# Hex-pendant-apa102-v1a.net
KiCad netlist of a schematic drawn in EAGLE
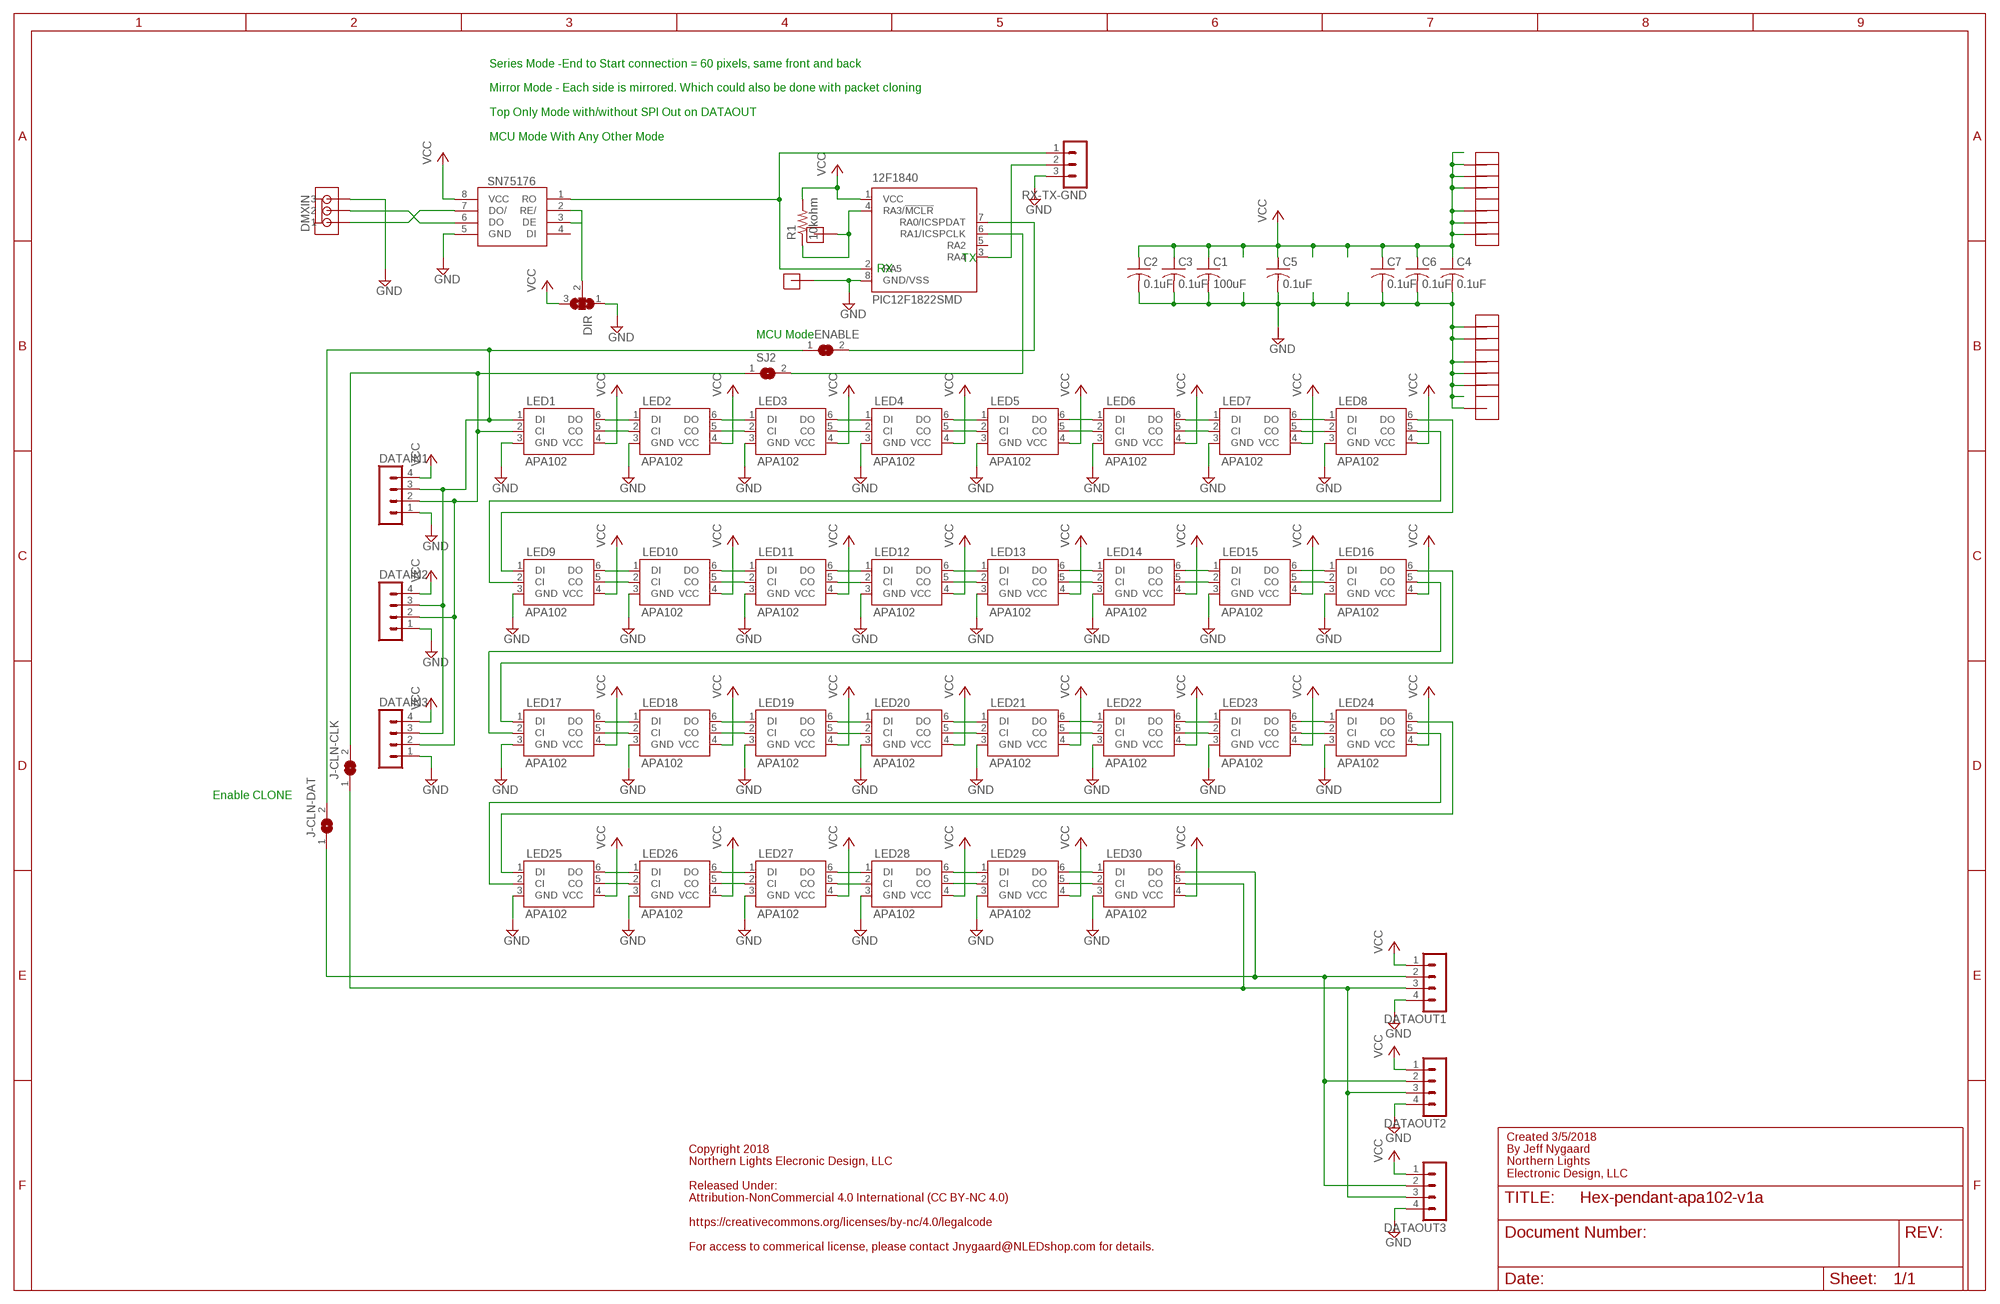
[diagram p0: schematic, sheet 1]

(export (version "E")
  (design (tool "Eeschema 10.0.6"))
  (components
    (comp (ref "12F1840")
      (value "PIC12F1822SMD")
      (footprint "eagle-import:SO-08")
      (fields (field (name "MF") "MICROCHIP") (field (name "MPN") "PIC12F675-E/SN"))
      (libsource (lib "eagle-import") (part "PIC12F1822SMD"))
    )
    (comp (ref "BUTTGND")
      (value "JUMPER")
      (footprint "eagle-import:JUMPER")
      (libsource (lib "eagle-import") (part "JUMPER"))
    )
    (comp (ref "BUTTON")
      (value "JUMPER")
      (footprint "eagle-import:JUMPER")
      (libsource (lib "eagle-import") (part "JUMPER"))
    )
    (comp (ref "C1")
      (value "100uF")
      (footprint "eagle-import:C1206")
      (libsource (lib "eagle-import") (part "C-USC1206"))
    )
    (comp (ref "C2")
      (value "0.1uF")
      (footprint "eagle-import:C1206")
      (libsource (lib "eagle-import") (part "C-USC1206"))
    )
    (comp (ref "C3")
      (value "0.1uF")
      (footprint "eagle-import:C1206")
      (libsource (lib "eagle-import") (part "C-USC1206"))
    )
    (comp (ref "C4")
      (value "0.1uF")
      (footprint "eagle-import:C1206")
      (libsource (lib "eagle-import") (part "C-USC1206"))
    )
    (comp (ref "C5")
      (value "0.1uF")
      (footprint "eagle-import:C1206")
      (libsource (lib "eagle-import") (part "C-USC1206"))
    )
    (comp (ref "C6")
      (value "0.1uF")
      (footprint "eagle-import:C1206")
      (libsource (lib "eagle-import") (part "C-USC1206"))
    )
    (comp (ref "C7")
      (value "0.1uF")
      (footprint "eagle-import:C1206")
      (libsource (lib "eagle-import") (part "C-USC1206"))
    )
    (comp (ref "DATAIN1")
      (value "MA04-1")
      (footprint "eagle-import:MA04-1")
      (libsource (lib "eagle-import") (part "MA04-1"))
    )
    (comp (ref "DATAIN2")
      (value "MA04-1")
      (footprint "eagle-import:MA04-1")
      (libsource (lib "eagle-import") (part "MA04-1"))
    )
    (comp (ref "DATAIN3")
      (value "MA04-1")
      (footprint "eagle-import:MA04-1")
      (libsource (lib "eagle-import") (part "MA04-1"))
    )
    (comp (ref "DATAOUT1")
      (value "MA04-1")
      (footprint "eagle-import:MA04-1")
      (libsource (lib "eagle-import") (part "MA04-1"))
    )
    (comp (ref "DATAOUT2")
      (value "MA04-1")
      (footprint "eagle-import:MA04-1")
      (libsource (lib "eagle-import") (part "MA04-1"))
    )
    (comp (ref "DATAOUT3")
      (value "MA04-1")
      (footprint "eagle-import:MA04-1")
      (libsource (lib "eagle-import") (part "MA04-1"))
    )
    (comp (ref "DIR")
      (value "SJ2W")
      (footprint "eagle-import:SJ_2")
      (libsource (lib "eagle-import") (part "SJ2W"))
    )
    (comp (ref "DMXIN")
      (value "MOLEXKK3")
      (footprint "eagle-import:MOLEXKK3")
      (libsource (lib "eagle-import") (part "MOLEXKK3"))
    )
    (comp (ref "ENABLE")
      (value "SJ")
      (footprint "eagle-import:SJ")
      (libsource (lib "eagle-import") (part "SJ"))
    )
    (comp (ref "J-CLN-CLK")
      (value "SJ")
      (footprint "eagle-import:SJ")
      (libsource (lib "eagle-import") (part "SJ"))
    )
    (comp (ref "J-CLN-DAT")
      (value "SJ")
      (footprint "eagle-import:SJ")
      (libsource (lib "eagle-import") (part "SJ"))
    )
    (comp (ref "JGND1")
      (value "1HEADER")
      (footprint "eagle-import:J1")
      (libsource (lib "eagle-import") (part "1HEADER"))
    )
    (comp (ref "JGND3")
      (value "1HEADER")
      (footprint "eagle-import:J1")
      (libsource (lib "eagle-import") (part "1HEADER"))
    )
    (comp (ref "JGND4")
      (value "1HEADER")
      (footprint "eagle-import:J1")
      (libsource (lib "eagle-import") (part "1HEADER"))
    )
    (comp (ref "JGND5")
      (value "1HEADER")
      (footprint "eagle-import:J1")
      (libsource (lib "eagle-import") (part "1HEADER"))
    )
    (comp (ref "JGND6")
      (value "1HEADER")
      (footprint "eagle-import:J1")
      (libsource (lib "eagle-import") (part "1HEADER"))
    )
    (comp (ref "JGND7")
      (value "1HEADER")
      (footprint "eagle-import:J1")
      (libsource (lib "eagle-import") (part "1HEADER"))
    )
    (comp (ref "JVCC1")
      (value "1HEADER")
      (footprint "eagle-import:J1")
      (libsource (lib "eagle-import") (part "1HEADER"))
    )
    (comp (ref "JVCC2")
      (value "1HEADER")
      (footprint "eagle-import:J1")
      (libsource (lib "eagle-import") (part "1HEADER"))
    )
    (comp (ref "JVCC3")
      (value "1HEADER")
      (footprint "eagle-import:J1")
      (libsource (lib "eagle-import") (part "1HEADER"))
    )
    (comp (ref "JVCC4")
      (value "1HEADER")
      (footprint "eagle-import:J1")
      (libsource (lib "eagle-import") (part "1HEADER"))
    )
    (comp (ref "JVCC5")
      (value "1HEADER")
      (footprint "eagle-import:J1")
      (libsource (lib "eagle-import") (part "1HEADER"))
    )
    (comp (ref "JVCC6")
      (value "1HEADER")
      (footprint "eagle-import:J1")
      (libsource (lib "eagle-import") (part "1HEADER"))
    )
    (comp (ref "LED1")
      (value "APA102")
      (footprint "eagle-import:APA102")
      (libsource (lib "eagle-import") (part "APA102"))
    )
    (comp (ref "LED2")
      (value "APA102")
      (footprint "eagle-import:APA102")
      (libsource (lib "eagle-import") (part "APA102"))
    )
    (comp (ref "LED3")
      (value "APA102")
      (footprint "eagle-import:APA102")
      (libsource (lib "eagle-import") (part "APA102"))
    )
    (comp (ref "LED4")
      (value "APA102")
      (footprint "eagle-import:APA102")
      (libsource (lib "eagle-import") (part "APA102"))
    )
    (comp (ref "LED5")
      (value "APA102")
      (footprint "eagle-import:APA102")
      (libsource (lib "eagle-import") (part "APA102"))
    )
    (comp (ref "LED6")
      (value "APA102")
      (footprint "eagle-import:APA102")
      (libsource (lib "eagle-import") (part "APA102"))
    )
    (comp (ref "LED7")
      (value "APA102")
      (footprint "eagle-import:APA102")
      (libsource (lib "eagle-import") (part "APA102"))
    )
    (comp (ref "LED8")
      (value "APA102")
      (footprint "eagle-import:APA102")
      (libsource (lib "eagle-import") (part "APA102"))
    )
    (comp (ref "LED9")
      (value "APA102")
      (footprint "eagle-import:APA102")
      (libsource (lib "eagle-import") (part "APA102"))
    )
    (comp (ref "LED10")
      (value "APA102")
      (footprint "eagle-import:APA102")
      (libsource (lib "eagle-import") (part "APA102"))
    )
    (comp (ref "LED11")
      (value "APA102")
      (footprint "eagle-import:APA102")
      (libsource (lib "eagle-import") (part "APA102"))
    )
    (comp (ref "LED12")
      (value "APA102")
      (footprint "eagle-import:APA102")
      (libsource (lib "eagle-import") (part "APA102"))
    )
    (comp (ref "LED13")
      (value "APA102")
      (footprint "eagle-import:APA102")
      (libsource (lib "eagle-import") (part "APA102"))
    )
    (comp (ref "LED14")
      (value "APA102")
      (footprint "eagle-import:APA102")
      (libsource (lib "eagle-import") (part "APA102"))
    )
    (comp (ref "LED15")
      (value "APA102")
      (footprint "eagle-import:APA102")
      (libsource (lib "eagle-import") (part "APA102"))
    )
    (comp (ref "LED16")
      (value "APA102")
      (footprint "eagle-import:APA102")
      (libsource (lib "eagle-import") (part "APA102"))
    )
    (comp (ref "LED17")
      (value "APA102")
      (footprint "eagle-import:APA102")
      (libsource (lib "eagle-import") (part "APA102"))
    )
    (comp (ref "LED18")
      (value "APA102")
      (footprint "eagle-import:APA102")
      (libsource (lib "eagle-import") (part "APA102"))
    )
    (comp (ref "LED19")
      (value "APA102")
      (footprint "eagle-import:APA102")
      (libsource (lib "eagle-import") (part "APA102"))
    )
    (comp (ref "LED20")
      (value "APA102")
      (footprint "eagle-import:APA102")
      (libsource (lib "eagle-import") (part "APA102"))
    )
    (comp (ref "LED21")
      (value "APA102")
      (footprint "eagle-import:APA102")
      (libsource (lib "eagle-import") (part "APA102"))
    )
    (comp (ref "LED22")
      (value "APA102")
      (footprint "eagle-import:APA102")
      (libsource (lib "eagle-import") (part "APA102"))
    )
    (comp (ref "LED23")
      (value "APA102")
      (footprint "eagle-import:APA102")
      (libsource (lib "eagle-import") (part "APA102"))
    )
    (comp (ref "LED24")
      (value "APA102")
      (footprint "eagle-import:APA102")
      (libsource (lib "eagle-import") (part "APA102"))
    )
    (comp (ref "LED25")
      (value "APA102")
      (footprint "eagle-import:APA102")
      (libsource (lib "eagle-import") (part "APA102"))
    )
    (comp (ref "LED26")
      (value "APA102")
      (footprint "eagle-import:APA102")
      (libsource (lib "eagle-import") (part "APA102"))
    )
    (comp (ref "LED27")
      (value "APA102")
      (footprint "eagle-import:APA102")
      (libsource (lib "eagle-import") (part "APA102"))
    )
    (comp (ref "LED28")
      (value "APA102")
      (footprint "eagle-import:APA102")
      (libsource (lib "eagle-import") (part "APA102"))
    )
    (comp (ref "LED29")
      (value "APA102")
      (footprint "eagle-import:APA102")
      (libsource (lib "eagle-import") (part "APA102"))
    )
    (comp (ref "LED30")
      (value "APA102")
      (footprint "eagle-import:APA102")
      (libsource (lib "eagle-import") (part "APA102"))
    )
    (comp (ref "R1")
      (value "10kohm")
      (footprint "eagle-import:R1206")
      (libsource (lib "eagle-import") (part "R-US_R1206"))
    )
    (comp (ref "RX-TX-GND")
      (value "MA03-12")
      (footprint "eagle-import:MA03-1-V2")
      (libsource (lib "eagle-import") (part "MA03-12"))
    )
    (comp (ref "SJ2") (value "SJ") (footprint "eagle-import:SJ") (libsource (lib "eagle-import") (part "SJ")))
    (comp (ref "TRANSCEIVER")
      (value "SN75176SMD")
      (footprint "eagle-import:SOIC-8")
      (libsource (lib "eagle-import") (part "SN75176SMD"))
    )
  )
  (nets
    (net (code "1") (name "GND") (class "Default")
      (node (ref "12F1840") (pin "8") (pinfunction "GND/VSS_8") (pintype "power_in"))
      (node (ref "BUTTGND") (pin "2") (pinfunction "J1_2") (pintype "bidirectional"))
      (node (ref "C1") (pin "2") (pinfunction "2_2") (pintype "passive"))
      (node (ref "C2") (pin "2") (pinfunction "2_2") (pintype "passive"))
      (node (ref "C3") (pin "2") (pinfunction "2_2") (pintype "passive"))
      (node (ref "C4") (pin "2") (pinfunction "2_2") (pintype "passive"))
      (node (ref "C5") (pin "2") (pinfunction "2_2") (pintype "passive"))
      (node (ref "C6") (pin "2") (pinfunction "2_2") (pintype "passive"))
      (node (ref "C7") (pin "2") (pinfunction "2_2") (pintype "passive"))
      (node (ref "DATAIN1") (pin "1") (pinfunction "1_1") (pintype "passive"))
      (node (ref "DATAIN2") (pin "1") (pinfunction "1_1") (pintype "passive"))
      (node (ref "DATAIN3") (pin "1") (pinfunction "1_1") (pintype "passive"))
      (node (ref "DATAOUT1") (pin "4") (pinfunction "4_4") (pintype "passive"))
      (node (ref "DATAOUT2") (pin "4") (pinfunction "4_4") (pintype "passive"))
      (node (ref "DATAOUT3") (pin "4") (pinfunction "4_4") (pintype "passive"))
      (node (ref "DIR") (pin "1") (pinfunction "1_1") (pintype "passive"))
      (node (ref "DMXIN") (pin "3") (pinfunction "3_3") (pintype "bidirectional"))
      (node (ref "JGND1") (pin "2") (pinfunction "J1_2") (pintype "bidirectional"))
      (node (ref "JGND3") (pin "2") (pinfunction "J1_2") (pintype "bidirectional"))
      (node (ref "JGND4") (pin "2") (pinfunction "J1_2") (pintype "bidirectional"))
      (node (ref "JGND6") (pin "2") (pinfunction "J1_2") (pintype "bidirectional"))
      (node (ref "JGND7") (pin "2") (pinfunction "J1_2") (pintype "bidirectional"))
      (node (ref "JVCC4") (pin "2") (pinfunction "J1_2") (pintype "bidirectional"))
      (node (ref "LED1") (pin "3") (pinfunction "GND_3") (pintype "bidirectional"))
      (node (ref "LED10") (pin "3") (pinfunction "GND_3") (pintype "bidirectional"))
      (node (ref "LED11") (pin "3") (pinfunction "GND_3") (pintype "bidirectional"))
      (node (ref "LED12") (pin "3") (pinfunction "GND_3") (pintype "bidirectional"))
      (node (ref "LED13") (pin "3") (pinfunction "GND_3") (pintype "bidirectional"))
      (node (ref "LED14") (pin "3") (pinfunction "GND_3") (pintype "bidirectional"))
      (node (ref "LED15") (pin "3") (pinfunction "GND_3") (pintype "bidirectional"))
      (node (ref "LED16") (pin "3") (pinfunction "GND_3") (pintype "bidirectional"))
      (node (ref "LED17") (pin "3") (pinfunction "GND_3") (pintype "bidirectional"))
      (node (ref "LED18") (pin "3") (pinfunction "GND_3") (pintype "bidirectional"))
      (node (ref "LED19") (pin "3") (pinfunction "GND_3") (pintype "bidirectional"))
      (node (ref "LED2") (pin "3") (pinfunction "GND_3") (pintype "bidirectional"))
      (node (ref "LED20") (pin "3") (pinfunction "GND_3") (pintype "bidirectional"))
      (node (ref "LED21") (pin "3") (pinfunction "GND_3") (pintype "bidirectional"))
      (node (ref "LED22") (pin "3") (pinfunction "GND_3") (pintype "bidirectional"))
      (node (ref "LED23") (pin "3") (pinfunction "GND_3") (pintype "bidirectional"))
      (node (ref "LED24") (pin "3") (pinfunction "GND_3") (pintype "bidirectional"))
      (node (ref "LED25") (pin "3") (pinfunction "GND_3") (pintype "bidirectional"))
      (node (ref "LED26") (pin "3") (pinfunction "GND_3") (pintype "bidirectional"))
      (node (ref "LED27") (pin "3") (pinfunction "GND_3") (pintype "bidirectional"))
      (node (ref "LED28") (pin "3") (pinfunction "GND_3") (pintype "bidirectional"))
      (node (ref "LED29") (pin "3") (pinfunction "GND_3") (pintype "bidirectional"))
      (node (ref "LED3") (pin "3") (pinfunction "GND_3") (pintype "bidirectional"))
      (node (ref "LED30") (pin "3") (pinfunction "GND_3") (pintype "bidirectional"))
      (node (ref "LED4") (pin "3") (pinfunction "GND_3") (pintype "bidirectional"))
      (node (ref "LED5") (pin "3") (pinfunction "GND_3") (pintype "bidirectional"))
      (node (ref "LED6") (pin "3") (pinfunction "GND_3") (pintype "bidirectional"))
      (node (ref "LED7") (pin "3") (pinfunction "GND_3") (pintype "bidirectional"))
      (node (ref "LED8") (pin "3") (pinfunction "GND_3") (pintype "bidirectional"))
      (node (ref "LED9") (pin "3") (pinfunction "GND_3") (pintype "bidirectional"))
      (node (ref "RX-TX-GND") (pin "3") (pinfunction "3_3") (pintype "passive"))
      (node (ref "TRANSCEIVER") (pin "5") (pinfunction "GND_5") (pintype "bidirectional"))
    )
    (net (code "2") (name "Net-(12F1840-RA0{slash}ICSPDAT)") (class "Default")
      (node (ref "12F1840") (pin "7") (pinfunction "RA0/ICSPDAT_7") (pintype "bidirectional"))
      (node (ref "ENABLE") (pin "2") (pinfunction "2_2") (pintype "passive"))
    )
    (net (code "3") (name "Net-(12F1840-RA1{slash}ICSPCLK)") (class "Default")
      (node (ref "12F1840") (pin "6") (pinfunction "RA1/ICSPCLK_6") (pintype "bidirectional"))
      (node (ref "SJ2") (pin "2") (pinfunction "2_2") (pintype "passive"))
    )
    (net (code "4") (name "Net-(12F1840-RA3{slash}~{MCLR})") (class "Default")
      (node (ref "12F1840") (pin "4") (pinfunction "RA3/~{MCLR}_4") (pintype "input"))
      (node (ref "BUTTON") (pin "2") (pinfunction "J1_2") (pintype "bidirectional"))
      (node (ref "R1") (pin "1") (pinfunction "1_1") (pintype "passive"))
    )
    (net (code "5") (name "Net-(12F1840-RA4)") (class "Default")
      (node (ref "12F1840") (pin "3") (pinfunction "RA4_3") (pintype "bidirectional"))
      (node (ref "RX-TX-GND") (pin "2") (pinfunction "2_2") (pintype "passive"))
    )
    (net (code "6") (name "Net-(12F1840-RA5)") (class "Default")
      (node (ref "12F1840") (pin "2") (pinfunction "RA5_2") (pintype "bidirectional"))
      (node (ref "RX-TX-GND") (pin "1") (pinfunction "1_1") (pintype "passive"))
      (node (ref "TRANSCEIVER") (pin "1") (pinfunction "RO_1") (pintype "bidirectional"))
    )
    (net (code "7") (name "Net-(LED1-CI)") (class "Default")
      (node (ref "DATAIN1") (pin "2") (pinfunction "2_2") (pintype "passive"))
      (node (ref "DATAIN2") (pin "2") (pinfunction "2_2") (pintype "passive"))
      (node (ref "DATAIN3") (pin "2") (pinfunction "2_2") (pintype "passive"))
      (node (ref "J-CLN-CLK") (pin "2") (pinfunction "2_2") (pintype "passive"))
      (node (ref "LED1") (pin "2") (pinfunction "CI_2") (pintype "bidirectional"))
      (node (ref "SJ2") (pin "1") (pinfunction "1_1") (pintype "passive"))
    )
    (net (code "8") (name "Net-(LED1-CO)") (class "Default")
      (node (ref "LED1") (pin "5") (pinfunction "CO_5") (pintype "bidirectional"))
      (node (ref "LED2") (pin "2") (pinfunction "CI_2") (pintype "bidirectional"))
    )
    (net (code "9") (name "Net-(LED1-DI)") (class "Default")
      (node (ref "DATAIN1") (pin "3") (pinfunction "3_3") (pintype "passive"))
      (node (ref "DATAIN2") (pin "3") (pinfunction "3_3") (pintype "passive"))
      (node (ref "DATAIN3") (pin "3") (pinfunction "3_3") (pintype "passive"))
      (node (ref "ENABLE") (pin "1") (pinfunction "1_1") (pintype "passive"))
      (node (ref "J-CLN-DAT") (pin "2") (pinfunction "2_2") (pintype "passive"))
      (node (ref "LED1") (pin "1") (pinfunction "DI_1") (pintype "bidirectional"))
    )
    (net (code "10") (name "Net-(LED1-DO)") (class "Default")
      (node (ref "LED1") (pin "6") (pinfunction "DO_6") (pintype "bidirectional"))
      (node (ref "LED2") (pin "1") (pinfunction "DI_1") (pintype "bidirectional"))
    )
    (net (code "11") (name "Net-(LED2-CO)") (class "Default")
      (node (ref "LED2") (pin "5") (pinfunction "CO_5") (pintype "bidirectional"))
      (node (ref "LED3") (pin "2") (pinfunction "CI_2") (pintype "bidirectional"))
    )
    (net (code "12") (name "Net-(LED2-DO)") (class "Default")
      (node (ref "LED2") (pin "6") (pinfunction "DO_6") (pintype "bidirectional"))
      (node (ref "LED3") (pin "1") (pinfunction "DI_1") (pintype "bidirectional"))
    )
    (net (code "13") (name "Net-(LED3-CO)") (class "Default")
      (node (ref "LED3") (pin "5") (pinfunction "CO_5") (pintype "bidirectional"))
      (node (ref "LED4") (pin "2") (pinfunction "CI_2") (pintype "bidirectional"))
    )
    (net (code "14") (name "Net-(LED3-DO)") (class "Default")
      (node (ref "LED3") (pin "6") (pinfunction "DO_6") (pintype "bidirectional"))
      (node (ref "LED4") (pin "1") (pinfunction "DI_1") (pintype "bidirectional"))
    )
    (net (code "15") (name "Net-(LED4-CO)") (class "Default")
      (node (ref "LED4") (pin "5") (pinfunction "CO_5") (pintype "bidirectional"))
      (node (ref "LED5") (pin "2") (pinfunction "CI_2") (pintype "bidirectional"))
    )
    (net (code "16") (name "Net-(LED4-DO)") (class "Default")
      (node (ref "LED4") (pin "6") (pinfunction "DO_6") (pintype "bidirectional"))
      (node (ref "LED5") (pin "1") (pinfunction "DI_1") (pintype "bidirectional"))
    )
    (net (code "17") (name "Net-(LED5-CO)") (class "Default")
      (node (ref "LED5") (pin "5") (pinfunction "CO_5") (pintype "bidirectional"))
      (node (ref "LED6") (pin "2") (pinfunction "CI_2") (pintype "bidirectional"))
    )
    (net (code "18") (name "Net-(LED5-DO)") (class "Default")
      (node (ref "LED5") (pin "6") (pinfunction "DO_6") (pintype "bidirectional"))
      (node (ref "LED6") (pin "1") (pinfunction "DI_1") (pintype "bidirectional"))
    )
    (net (code "19") (name "Net-(LED6-CO)") (class "Default")
      (node (ref "LED6") (pin "5") (pinfunction "CO_5") (pintype "bidirectional"))
      (node (ref "LED7") (pin "2") (pinfunction "CI_2") (pintype "bidirectional"))
    )
    (net (code "20") (name "Net-(LED6-DO)") (class "Default")
      (node (ref "LED6") (pin "6") (pinfunction "DO_6") (pintype "bidirectional"))
      (node (ref "LED7") (pin "1") (pinfunction "DI_1") (pintype "bidirectional"))
    )
    (net (code "21") (name "Net-(LED7-CO)") (class "Default")
      (node (ref "LED7") (pin "5") (pinfunction "CO_5") (pintype "bidirectional"))
      (node (ref "LED8") (pin "2") (pinfunction "CI_2") (pintype "bidirectional"))
    )
    (net (code "22") (name "Net-(LED7-DO)") (class "Default")
      (node (ref "LED7") (pin "6") (pinfunction "DO_6") (pintype "bidirectional"))
      (node (ref "LED8") (pin "1") (pinfunction "DI_1") (pintype "bidirectional"))
    )
    (net (code "23") (name "Net-(LED8-CO)") (class "Default")
      (node (ref "LED8") (pin "5") (pinfunction "CO_5") (pintype "bidirectional"))
      (node (ref "LED9") (pin "2") (pinfunction "CI_2") (pintype "bidirectional"))
    )
    (net (code "24") (name "Net-(LED8-DO)") (class "Default")
      (node (ref "LED8") (pin "6") (pinfunction "DO_6") (pintype "bidirectional"))
      (node (ref "LED9") (pin "1") (pinfunction "DI_1") (pintype "bidirectional"))
    )
    (net (code "25") (name "Net-(LED10-CI)") (class "Default")
      (node (ref "LED10") (pin "2") (pinfunction "CI_2") (pintype "bidirectional"))
      (node (ref "LED9") (pin "5") (pinfunction "CO_5") (pintype "bidirectional"))
    )
    (net (code "26") (name "Net-(LED10-CO)") (class "Default")
      (node (ref "LED10") (pin "5") (pinfunction "CO_5") (pintype "bidirectional"))
      (node (ref "LED11") (pin "2") (pinfunction "CI_2") (pintype "bidirectional"))
    )
    (net (code "27") (name "Net-(LED10-DI)") (class "Default")
      (node (ref "LED10") (pin "1") (pinfunction "DI_1") (pintype "bidirectional"))
      (node (ref "LED9") (pin "6") (pinfunction "DO_6") (pintype "bidirectional"))
    )
    (net (code "28") (name "Net-(LED10-DO)") (class "Default")
      (node (ref "LED10") (pin "6") (pinfunction "DO_6") (pintype "bidirectional"))
      (node (ref "LED11") (pin "1") (pinfunction "DI_1") (pintype "bidirectional"))
    )
    (net (code "29") (name "Net-(LED11-CO)") (class "Default")
      (node (ref "LED11") (pin "5") (pinfunction "CO_5") (pintype "bidirectional"))
      (node (ref "LED12") (pin "2") (pinfunction "CI_2") (pintype "bidirectional"))
    )
    (net (code "30") (name "Net-(LED11-DO)") (class "Default")
      (node (ref "LED11") (pin "6") (pinfunction "DO_6") (pintype "bidirectional"))
      (node (ref "LED12") (pin "1") (pinfunction "DI_1") (pintype "bidirectional"))
    )
    (net (code "31") (name "Net-(LED12-CO)") (class "Default")
      (node (ref "LED12") (pin "5") (pinfunction "CO_5") (pintype "bidirectional"))
      (node (ref "LED13") (pin "2") (pinfunction "CI_2") (pintype "bidirectional"))
    )
    (net (code "32") (name "Net-(LED12-DO)") (class "Default")
      (node (ref "LED12") (pin "6") (pinfunction "DO_6") (pintype "bidirectional"))
      (node (ref "LED13") (pin "1") (pinfunction "DI_1") (pintype "bidirectional"))
    )
    (net (code "33") (name "Net-(LED13-CO)") (class "Default")
      (node (ref "LED13") (pin "5") (pinfunction "CO_5") (pintype "bidirectional"))
      (node (ref "LED14") (pin "2") (pinfunction "CI_2") (pintype "bidirectional"))
    )
    (net (code "34") (name "Net-(LED13-DO)") (class "Default")
      (node (ref "LED13") (pin "6") (pinfunction "DO_6") (pintype "bidirectional"))
      (node (ref "LED14") (pin "1") (pinfunction "DI_1") (pintype "bidirectional"))
    )
    (net (code "35") (name "Net-(LED14-CO)") (class "Default")
      (node (ref "LED14") (pin "5") (pinfunction "CO_5") (pintype "bidirectional"))
      (node (ref "LED15") (pin "2") (pinfunction "CI_2") (pintype "bidirectional"))
    )
    (net (code "36") (name "Net-(LED14-DO)") (class "Default")
      (node (ref "LED14") (pin "6") (pinfunction "DO_6") (pintype "bidirectional"))
      (node (ref "LED15") (pin "1") (pinfunction "DI_1") (pintype "bidirectional"))
    )
    (net (code "37") (name "Net-(LED15-CO)") (class "Default")
      (node (ref "LED15") (pin "5") (pinfunction "CO_5") (pintype "bidirectional"))
      (node (ref "LED16") (pin "2") (pinfunction "CI_2") (pintype "bidirectional"))
    )
    (net (code "38") (name "Net-(LED15-DO)") (class "Default")
      (node (ref "LED15") (pin "6") (pinfunction "DO_6") (pintype "bidirectional"))
      (node (ref "LED16") (pin "1") (pinfunction "DI_1") (pintype "bidirectional"))
    )
    (net (code "39") (name "Net-(LED16-CO)") (class "Default")
      (node (ref "LED16") (pin "5") (pinfunction "CO_5") (pintype "bidirectional"))
      (node (ref "LED17") (pin "2") (pinfunction "CI_2") (pintype "bidirectional"))
    )
    (net (code "40") (name "Net-(LED16-DO)") (class "Default")
      (node (ref "LED16") (pin "6") (pinfunction "DO_6") (pintype "bidirectional"))
      (node (ref "LED17") (pin "1") (pinfunction "DI_1") (pintype "bidirectional"))
    )
    (net (code "41") (name "Net-(LED17-CO)") (class "Default")
      (node (ref "LED17") (pin "5") (pinfunction "CO_5") (pintype "bidirectional"))
      (node (ref "LED18") (pin "2") (pinfunction "CI_2") (pintype "bidirectional"))
    )
    (net (code "42") (name "Net-(LED17-DO)") (class "Default")
      (node (ref "LED17") (pin "6") (pinfunction "DO_6") (pintype "bidirectional"))
      (node (ref "LED18") (pin "1") (pinfunction "DI_1") (pintype "bidirectional"))
    )
    (net (code "43") (name "Net-(LED18-CO)") (class "Default")
      (node (ref "LED18") (pin "5") (pinfunction "CO_5") (pintype "bidirectional"))
      (node (ref "LED19") (pin "2") (pinfunction "CI_2") (pintype "bidirectional"))
    )
    (net (code "44") (name "Net-(LED18-DO)") (class "Default")
      (node (ref "LED18") (pin "6") (pinfunction "DO_6") (pintype "bidirectional"))
      (node (ref "LED19") (pin "1") (pinfunction "DI_1") (pintype "bidirectional"))
    )
    (net (code "45") (name "Net-(LED19-CO)") (class "Default")
      (node (ref "LED19") (pin "5") (pinfunction "CO_5") (pintype "bidirectional"))
      (node (ref "LED20") (pin "2") (pinfunction "CI_2") (pintype "bidirectional"))
    )
    (net (code "46") (name "Net-(LED19-DO)") (class "Default")
      (node (ref "LED19") (pin "6") (pinfunction "DO_6") (pintype "bidirectional"))
      (node (ref "LED20") (pin "1") (pinfunction "DI_1") (pintype "bidirectional"))
    )
    (net (code "47") (name "Net-(LED20-CO)") (class "Default")
      (node (ref "LED20") (pin "5") (pinfunction "CO_5") (pintype "bidirectional"))
      (node (ref "LED21") (pin "2") (pinfunction "CI_2") (pintype "bidirectional"))
    )
    (net (code "48") (name "Net-(LED20-DO)") (class "Default")
      (node (ref "LED20") (pin "6") (pinfunction "DO_6") (pintype "bidirectional"))
      (node (ref "LED21") (pin "1") (pinfunction "DI_1") (pintype "bidirectional"))
    )
    (net (code "49") (name "Net-(LED21-CO)") (class "Default")
      (node (ref "LED21") (pin "5") (pinfunction "CO_5") (pintype "bidirectional"))
      (node (ref "LED22") (pin "2") (pinfunction "CI_2") (pintype "bidirectional"))
    )
    (net (code "50") (name "Net-(LED21-DO)") (class "Default")
      (node (ref "LED21") (pin "6") (pinfunction "DO_6") (pintype "bidirectional"))
      (node (ref "LED22") (pin "1") (pinfunction "DI_1") (pintype "bidirectional"))
    )
    (net (code "51") (name "Net-(LED22-CO)") (class "Default")
      (node (ref "LED22") (pin "5") (pinfunction "CO_5") (pintype "bidirectional"))
      (node (ref "LED23") (pin "2") (pinfunction "CI_2") (pintype "bidirectional"))
    )
    (net (code "52") (name "Net-(LED22-DO)") (class "Default")
      (node (ref "LED22") (pin "6") (pinfunction "DO_6") (pintype "bidirectional"))
      (node (ref "LED23") (pin "1") (pinfunction "DI_1") (pintype "bidirectional"))
    )
    (net (code "53") (name "Net-(LED23-CO)") (class "Default")
      (node (ref "LED23") (pin "5") (pinfunction "CO_5") (pintype "bidirectional"))
      (node (ref "LED24") (pin "2") (pinfunction "CI_2") (pintype "bidirectional"))
    )
    (net (code "54") (name "Net-(LED23-DO)") (class "Default")
      (node (ref "LED23") (pin "6") (pinfunction "DO_6") (pintype "bidirectional"))
      (node (ref "LED24") (pin "1") (pinfunction "DI_1") (pintype "bidirectional"))
    )
    (net (code "55") (name "Net-(LED24-CO)") (class "Default")
      (node (ref "LED24") (pin "5") (pinfunction "CO_5") (pintype "bidirectional"))
      (node (ref "LED25") (pin "2") (pinfunction "CI_2") (pintype "bidirectional"))
    )
    (net (code "56") (name "Net-(LED24-DO)") (class "Default")
      (node (ref "LED24") (pin "6") (pinfunction "DO_6") (pintype "bidirectional"))
      (node (ref "LED25") (pin "1") (pinfunction "DI_1") (pintype "bidirectional"))
    )
    (net (code "57") (name "Net-(LED25-CO)") (class "Default")
      (node (ref "LED25") (pin "5") (pinfunction "CO_5") (pintype "bidirectional"))
      (node (ref "LED26") (pin "2") (pinfunction "CI_2") (pintype "bidirectional"))
    )
    (net (code "58") (name "Net-(LED25-DO)") (class "Default")
      (node (ref "LED25") (pin "6") (pinfunction "DO_6") (pintype "bidirectional"))
      (node (ref "LED26") (pin "1") (pinfunction "DI_1") (pintype "bidirectional"))
    )
    (net (code "59") (name "Net-(LED26-CO)") (class "Default")
      (node (ref "LED26") (pin "5") (pinfunction "CO_5") (pintype "bidirectional"))
      (node (ref "LED27") (pin "2") (pinfunction "CI_2") (pintype "bidirectional"))
    )
    (net (code "60") (name "Net-(LED26-DO)") (class "Default")
      (node (ref "LED26") (pin "6") (pinfunction "DO_6") (pintype "bidirectional"))
      (node (ref "LED27") (pin "1") (pinfunction "DI_1") (pintype "bidirectional"))
    )
    (net (code "61") (name "Net-(LED27-CO)") (class "Default")
      (node (ref "LED27") (pin "5") (pinfunction "CO_5") (pintype "bidirectional"))
      (node (ref "LED28") (pin "2") (pinfunction "CI_2") (pintype "bidirectional"))
    )
    (net (code "62") (name "Net-(LED27-DO)") (class "Default")
      (node (ref "LED27") (pin "6") (pinfunction "DO_6") (pintype "bidirectional"))
      (node (ref "LED28") (pin "1") (pinfunction "DI_1") (pintype "bidirectional"))
    )
    (net (code "63") (name "Net-(LED28-CO)") (class "Default")
      (node (ref "LED28") (pin "5") (pinfunction "CO_5") (pintype "bidirectional"))
      (node (ref "LED29") (pin "2") (pinfunction "CI_2") (pintype "bidirectional"))
    )
    (net (code "64") (name "Net-(LED28-DO)") (class "Default")
      (node (ref "LED28") (pin "6") (pinfunction "DO_6") (pintype "bidirectional"))
      (node (ref "LED29") (pin "1") (pinfunction "DI_1") (pintype "bidirectional"))
    )
    (net (code "65") (name "Net-(LED29-CO)") (class "Default")
      (node (ref "LED29") (pin "5") (pinfunction "CO_5") (pintype "bidirectional"))
      (node (ref "LED30") (pin "2") (pinfunction "CI_2") (pintype "bidirectional"))
    )
    (net (code "66") (name "Net-(LED29-DO)") (class "Default")
      (node (ref "LED29") (pin "6") (pinfunction "DO_6") (pintype "bidirectional"))
      (node (ref "LED30") (pin "1") (pinfunction "DI_1") (pintype "bidirectional"))
    )
    (net (code "67") (name "Net-(LED30-CO)") (class "Default")
      (node (ref "DATAOUT1") (pin "3") (pinfunction "3_3") (pintype "passive"))
      (node (ref "DATAOUT2") (pin "3") (pinfunction "3_3") (pintype "passive"))
      (node (ref "DATAOUT3") (pin "3") (pinfunction "3_3") (pintype "passive"))
      (node (ref "J-CLN-CLK") (pin "1") (pinfunction "1_1") (pintype "passive"))
      (node (ref "LED30") (pin "5") (pinfunction "CO_5") (pintype "bidirectional"))
    )
    (net (code "68") (name "Net-(LED30-DO)") (class "Default")
      (node (ref "DATAOUT1") (pin "2") (pinfunction "2_2") (pintype "passive"))
      (node (ref "DATAOUT2") (pin "2") (pinfunction "2_2") (pintype "passive"))
      (node (ref "DATAOUT3") (pin "2") (pinfunction "2_2") (pintype "passive"))
      (node (ref "J-CLN-DAT") (pin "1") (pinfunction "1_1") (pintype "passive"))
      (node (ref "LED30") (pin "6") (pinfunction "DO_6") (pintype "bidirectional"))
    )
    (net (code "69") (name "Net-(TRANSCEIVER-DE)") (class "Default")
      (node (ref "DIR") (pin "2") (pinfunction "2_2") (pintype "passive"))
      (node (ref "TRANSCEIVER") (pin "2") (pinfunction "RE/_2") (pintype "bidirectional"))
      (node (ref "TRANSCEIVER") (pin "3") (pinfunction "DE_3") (pintype "bidirectional"))
    )
    (net (code "70") (name "Net-(TRANSCEIVER-DO)") (class "Default")
      (node (ref "DMXIN") (pin "2") (pinfunction "2_2") (pintype "bidirectional"))
      (node (ref "TRANSCEIVER") (pin "6") (pinfunction "DO_6") (pintype "bidirectional"))
    )
    (net (code "71") (name "Net-(TRANSCEIVER-DO{slash})") (class "Default")
      (node (ref "DMXIN") (pin "1") (pinfunction "1_1") (pintype "bidirectional"))
      (node (ref "TRANSCEIVER") (pin "7") (pinfunction "DO/_7") (pintype "bidirectional"))
    )
    (net (code "72") (name "VCC") (class "Default")
      (node (ref "12F1840") (pin "1") (pinfunction "VCC_1") (pintype "power_in"))
      (node (ref "C1") (pin "1") (pinfunction "1_1") (pintype "passive"))
      (node (ref "C2") (pin "1") (pinfunction "1_1") (pintype "passive"))
      (node (ref "C3") (pin "1") (pinfunction "1_1") (pintype "passive"))
      (node (ref "C4") (pin "1") (pinfunction "1_1") (pintype "passive"))
      (node (ref "C5") (pin "1") (pinfunction "1_1") (pintype "passive"))
      (node (ref "C6") (pin "1") (pinfunction "1_1") (pintype "passive"))
      (node (ref "C7") (pin "1") (pinfunction "1_1") (pintype "passive"))
      (node (ref "DATAIN1") (pin "4") (pinfunction "4_4") (pintype "passive"))
      (node (ref "DATAIN2") (pin "4") (pinfunction "4_4") (pintype "passive"))
      (node (ref "DATAIN3") (pin "4") (pinfunction "4_4") (pintype "passive"))
      (node (ref "DATAOUT1") (pin "1") (pinfunction "1_1") (pintype "passive"))
      (node (ref "DATAOUT2") (pin "1") (pinfunction "1_1") (pintype "passive"))
      (node (ref "DATAOUT3") (pin "1") (pinfunction "1_1") (pintype "passive"))
      (node (ref "DIR") (pin "3") (pinfunction "3_3") (pintype "passive"))
      (node (ref "JGND5") (pin "2") (pinfunction "J1_2") (pintype "bidirectional"))
      (node (ref "JVCC1") (pin "2") (pinfunction "J1_2") (pintype "bidirectional"))
      (node (ref "JVCC2") (pin "2") (pinfunction "J1_2") (pintype "bidirectional"))
      (node (ref "JVCC3") (pin "2") (pinfunction "J1_2") (pintype "bidirectional"))
      (node (ref "JVCC5") (pin "2") (pinfunction "J1_2") (pintype "bidirectional"))
      (node (ref "JVCC6") (pin "2") (pinfunction "J1_2") (pintype "bidirectional"))
      (node (ref "LED1") (pin "4") (pinfunction "VCC_4") (pintype "bidirectional"))
      (node (ref "LED10") (pin "4") (pinfunction "VCC_4") (pintype "bidirectional"))
      (node (ref "LED11") (pin "4") (pinfunction "VCC_4") (pintype "bidirectional"))
      (node (ref "LED12") (pin "4") (pinfunction "VCC_4") (pintype "bidirectional"))
      (node (ref "LED13") (pin "4") (pinfunction "VCC_4") (pintype "bidirectional"))
      (node (ref "LED14") (pin "4") (pinfunction "VCC_4") (pintype "bidirectional"))
      (node (ref "LED15") (pin "4") (pinfunction "VCC_4") (pintype "bidirectional"))
      (node (ref "LED16") (pin "4") (pinfunction "VCC_4") (pintype "bidirectional"))
      (node (ref "LED17") (pin "4") (pinfunction "VCC_4") (pintype "bidirectional"))
      (node (ref "LED18") (pin "4") (pinfunction "VCC_4") (pintype "bidirectional"))
      (node (ref "LED19") (pin "4") (pinfunction "VCC_4") (pintype "bidirectional"))
      (node (ref "LED2") (pin "4") (pinfunction "VCC_4") (pintype "bidirectional"))
      (node (ref "LED20") (pin "4") (pinfunction "VCC_4") (pintype "bidirectional"))
      (node (ref "LED21") (pin "4") (pinfunction "VCC_4") (pintype "bidirectional"))
      (node (ref "LED22") (pin "4") (pinfunction "VCC_4") (pintype "bidirectional"))
      (node (ref "LED23") (pin "4") (pinfunction "VCC_4") (pintype "bidirectional"))
      (node (ref "LED24") (pin "4") (pinfunction "VCC_4") (pintype "bidirectional"))
      (node (ref "LED25") (pin "4") (pinfunction "VCC_4") (pintype "bidirectional"))
      (node (ref "LED26") (pin "4") (pinfunction "VCC_4") (pintype "bidirectional"))
      (node (ref "LED27") (pin "4") (pinfunction "VCC_4") (pintype "bidirectional"))
      (node (ref "LED28") (pin "4") (pinfunction "VCC_4") (pintype "bidirectional"))
      (node (ref "LED29") (pin "4") (pinfunction "VCC_4") (pintype "bidirectional"))
      (node (ref "LED3") (pin "4") (pinfunction "VCC_4") (pintype "bidirectional"))
      (node (ref "LED30") (pin "4") (pinfunction "VCC_4") (pintype "bidirectional"))
      (node (ref "LED4") (pin "4") (pinfunction "VCC_4") (pintype "bidirectional"))
      (node (ref "LED5") (pin "4") (pinfunction "VCC_4") (pintype "bidirectional"))
      (node (ref "LED6") (pin "4") (pinfunction "VCC_4") (pintype "bidirectional"))
      (node (ref "LED7") (pin "4") (pinfunction "VCC_4") (pintype "bidirectional"))
      (node (ref "LED8") (pin "4") (pinfunction "VCC_4") (pintype "bidirectional"))
      (node (ref "LED9") (pin "4") (pinfunction "VCC_4") (pintype "bidirectional"))
      (node (ref "R1") (pin "2") (pinfunction "2_2") (pintype "passive"))
      (node (ref "TRANSCEIVER") (pin "8") (pinfunction "VCC_8") (pintype "bidirectional"))
    )
    (net (code "73") (name "unconnected-(12F1840-RA2-Pad5)") (class "Default")
      (node (ref "12F1840") (pin "5") (pinfunction "RA2_5") (pintype "bidirectional"))
    )
    (net (code "74") (name "unconnected-(TRANSCEIVER-DI-Pad4)") (class "Default")
      (node (ref "TRANSCEIVER") (pin "4") (pinfunction "DI_4") (pintype "bidirectional"))
    )
  )
)
